# rcplugs-esp12-v001.net
KiCad netlist of a schematic drawn in EAGLE
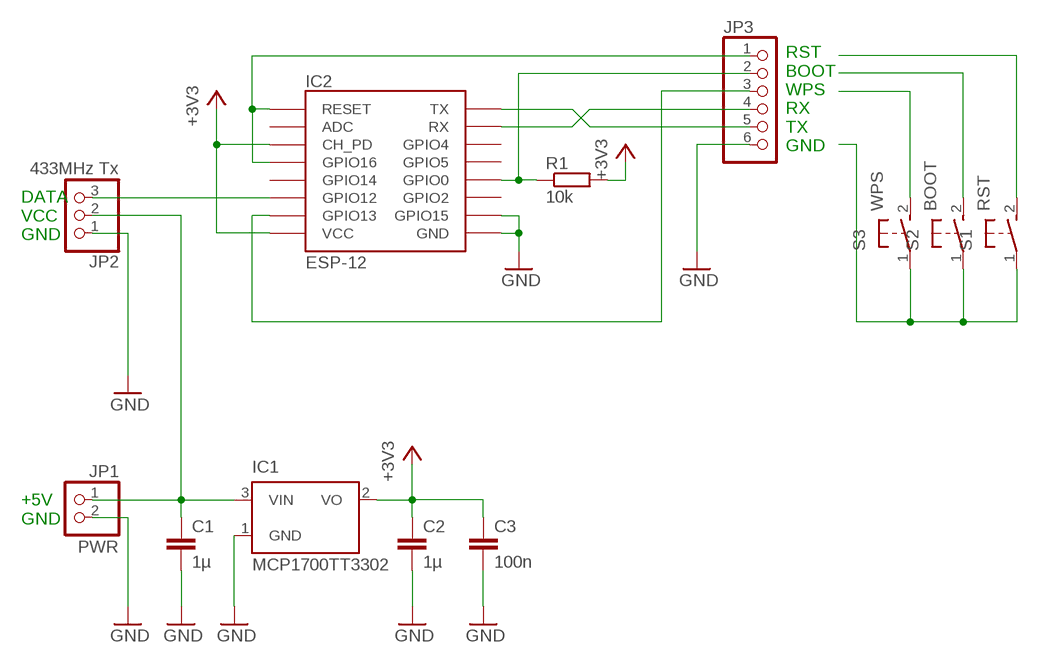
[diagram p0: schematic, sheet 1]

(export (version "E")
  (design (tool "Eeschema 10.0.6"))
  (components
    (comp (ref "C1")
      (value "1µ")
      (footprint "eagle-import:C0805")
      (libsource (lib "eagle-import") (part "C-EUC0805"))
    )
    (comp (ref "C2")
      (value "1µ")
      (footprint "eagle-import:C0805")
      (libsource (lib "eagle-import") (part "C-EUC0805"))
    )
    (comp (ref "C3")
      (value "100n")
      (footprint "eagle-import:C0805")
      (libsource (lib "eagle-import") (part "C-EUC0805"))
    )
    (comp (ref "IC1")
      (value "MCP1700TT3302")
      (footprint "eagle-import:SOT23")
      (libsource (lib "eagle-import") (part "MCP1700TT"))
    )
    (comp (ref "IC2")
      (value "ESP-12")
      (footprint "eagle-import:ESP-12")
      (libsource (lib "eagle-import") (part "ESP-12"))
    )
    (comp (ref "JP1")
      (value "PWR")
      (footprint "eagle-import:1X02")
      (libsource (lib "eagle-import") (part "PINHD-1X2"))
    )
    (comp (ref "JP2")
      (value "433MHz Tx")
      (footprint "eagle-import:1X03")
      (libsource (lib "eagle-import") (part "PINHD-1X3"))
    )
    (comp (ref "JP3")
      (value "PINHD-1X6")
      (footprint "eagle-import:1X06")
      (libsource (lib "eagle-import") (part "PINHD-1X6"))
    )
    (comp (ref "R1")
      (value "10k")
      (footprint "eagle-import:R0805HS")
      (libsource (lib "eagle-import") (part "R-EU_R0805HS"))
    )
    (comp (ref "S1")
      (value "RST")
      (footprint "eagle-import:TS1")
      (libsource (lib "eagle-import") (part "TS1"))
    )
    (comp (ref "S2")
      (value "BOOT")
      (footprint "eagle-import:TS1")
      (libsource (lib "eagle-import") (part "TS1"))
    )
    (comp (ref "S3")
      (value "WPS")
      (footprint "eagle-import:TS1")
      (libsource (lib "eagle-import") (part "TS1"))
    )
  )
  (nets
    (net (code "1") (name "+3V3") (class "Default")
      (node (ref "C2") (pin "1") (pinfunction "1_1") (pintype "passive"))
      (node (ref "C3") (pin "1") (pinfunction "1_1") (pintype "passive"))
      (node (ref "IC1") (pin "2") (pinfunction "VO_2") (pintype "output"))
      (node (ref "IC2") (pin "CH_PD") (pinfunction "CH_PD_CH_PD") (pintype "bidirectional"))
      (node (ref "IC2") (pin "VCC") (pinfunction "VCC_VCC") (pintype "bidirectional"))
      (node (ref "R1") (pin "2") (pinfunction "2_2") (pintype "passive"))
    )
    (net (code "2") (name "GND") (class "Default")
      (node (ref "C1") (pin "2") (pinfunction "2_2") (pintype "passive"))
      (node (ref "C2") (pin "2") (pinfunction "2_2") (pintype "passive"))
      (node (ref "C3") (pin "2") (pinfunction "2_2") (pintype "passive"))
      (node (ref "IC1") (pin "1") (pinfunction "GND_1") (pintype "passive"))
      (node (ref "IC2") (pin "GND") (pinfunction "GND_GND") (pintype "bidirectional"))
      (node (ref "IC2") (pin "GPIO15") (pinfunction "GPIO15_GPIO15") (pintype "bidirectional"))
      (node (ref "JP1") (pin "2") (pinfunction "2_2") (pintype "passive"))
      (node (ref "JP2") (pin "1") (pinfunction "1_1") (pintype "passive"))
      (node (ref "JP3") (pin "6") (pinfunction "6_6") (pintype "passive"))
    )
    (net (code "3") (name "Net-(IC1-VIN)") (class "Default")
      (node (ref "C1") (pin "1") (pinfunction "1_1") (pintype "passive"))
      (node (ref "IC1") (pin "3") (pinfunction "VIN_3") (pintype "input"))
      (node (ref "JP1") (pin "1") (pinfunction "1_1") (pintype "passive"))
      (node (ref "JP2") (pin "2") (pinfunction "2_2") (pintype "passive"))
    )
    (net (code "4") (name "Net-(IC2-PadGPIO0)") (class "Default")
      (node (ref "IC2") (pin "GPIO0") (pinfunction "GPIO0_GPIO0") (pintype "bidirectional"))
      (node (ref "JP3") (pin "2") (pinfunction "2_2") (pintype "passive"))
      (node (ref "R1") (pin "1") (pinfunction "1_1") (pintype "passive"))
    )
    (net (code "5") (name "Net-(IC2-PadGPIO12)") (class "Default")
      (node (ref "IC2") (pin "GPIO12") (pinfunction "GPIO12_GPIO12") (pintype "bidirectional"))
      (node (ref "JP2") (pin "3") (pinfunction "3_3") (pintype "passive"))
    )
    (net (code "6") (name "Net-(IC2-PadGPIO13)") (class "Default")
      (node (ref "IC2") (pin "GPIO13") (pinfunction "GPIO13_GPIO13") (pintype "bidirectional"))
      (node (ref "JP3") (pin "3") (pinfunction "3_3") (pintype "passive"))
    )
    (net (code "7") (name "Net-(IC2-PadGPIO16)") (class "Default")
      (node (ref "IC2") (pin "GPIO16") (pinfunction "GPIO16_GPIO16") (pintype "bidirectional"))
      (node (ref "IC2") (pin "RESET") (pinfunction "RESET_RESET") (pintype "bidirectional"))
      (node (ref "JP3") (pin "1") (pinfunction "1_1") (pintype "passive"))
    )
    (net (code "8") (name "Net-(IC2-PadRX)") (class "Default")
      (node (ref "IC2") (pin "RX") (pinfunction "RX_RX") (pintype "bidirectional"))
      (node (ref "JP3") (pin "4") (pinfunction "4_4") (pintype "passive"))
    )
    (net (code "9") (name "Net-(IC2-PadTX)") (class "Default")
      (node (ref "IC2") (pin "TX") (pinfunction "TX_TX") (pintype "bidirectional"))
      (node (ref "JP3") (pin "5") (pinfunction "5_5") (pintype "passive"))
    )
    (net (code "10") (name "Net-(S1-Pad1)") (class "Default")
      (node (ref "S1") (pin "1") (pinfunction "1_1") (pintype "passive"))
      (node (ref "S2") (pin "1") (pinfunction "1_1") (pintype "passive"))
      (node (ref "S3") (pin "1") (pinfunction "1_1") (pintype "passive"))
    )
    (net (code "11") (name "unconnected-(IC2-PadADC)") (class "Default")
      (node (ref "IC2") (pin "ADC") (pinfunction "ADC_ADC") (pintype "bidirectional"))
    )
    (net (code "12") (name "unconnected-(IC2-PadGPIO2)") (class "Default")
      (node (ref "IC2") (pin "GPIO2") (pinfunction "GPIO2_GPIO2") (pintype "bidirectional"))
    )
    (net (code "13") (name "unconnected-(IC2-PadGPIO4)") (class "Default")
      (node (ref "IC2") (pin "GPIO4") (pinfunction "GPIO4_GPIO4") (pintype "bidirectional"))
    )
    (net (code "14") (name "unconnected-(IC2-PadGPIO5)") (class "Default")
      (node (ref "IC2") (pin "GPIO5") (pinfunction "GPIO5_GPIO5") (pintype "bidirectional"))
    )
    (net (code "15") (name "unconnected-(IC2-PadGPIO14)") (class "Default")
      (node (ref "IC2") (pin "GPIO14") (pinfunction "GPIO14_GPIO14") (pintype "bidirectional"))
    )
    (net (code "16") (name "unconnected-(S1-Pad2)") (class "Default")
      (node (ref "S1") (pin "2") (pinfunction "2_2") (pintype "passive"))
    )
    (net (code "17") (name "unconnected-(S2-Pad2)") (class "Default")
      (node (ref "S2") (pin "2") (pinfunction "2_2") (pintype "passive"))
    )
    (net (code "18") (name "unconnected-(S3-Pad2)") (class "Default")
      (node (ref "S3") (pin "2") (pinfunction "2_2") (pintype "passive"))
    )
  )
)
